# project_8.net
KiCad netlist of a schematic drawn in Altium Designer
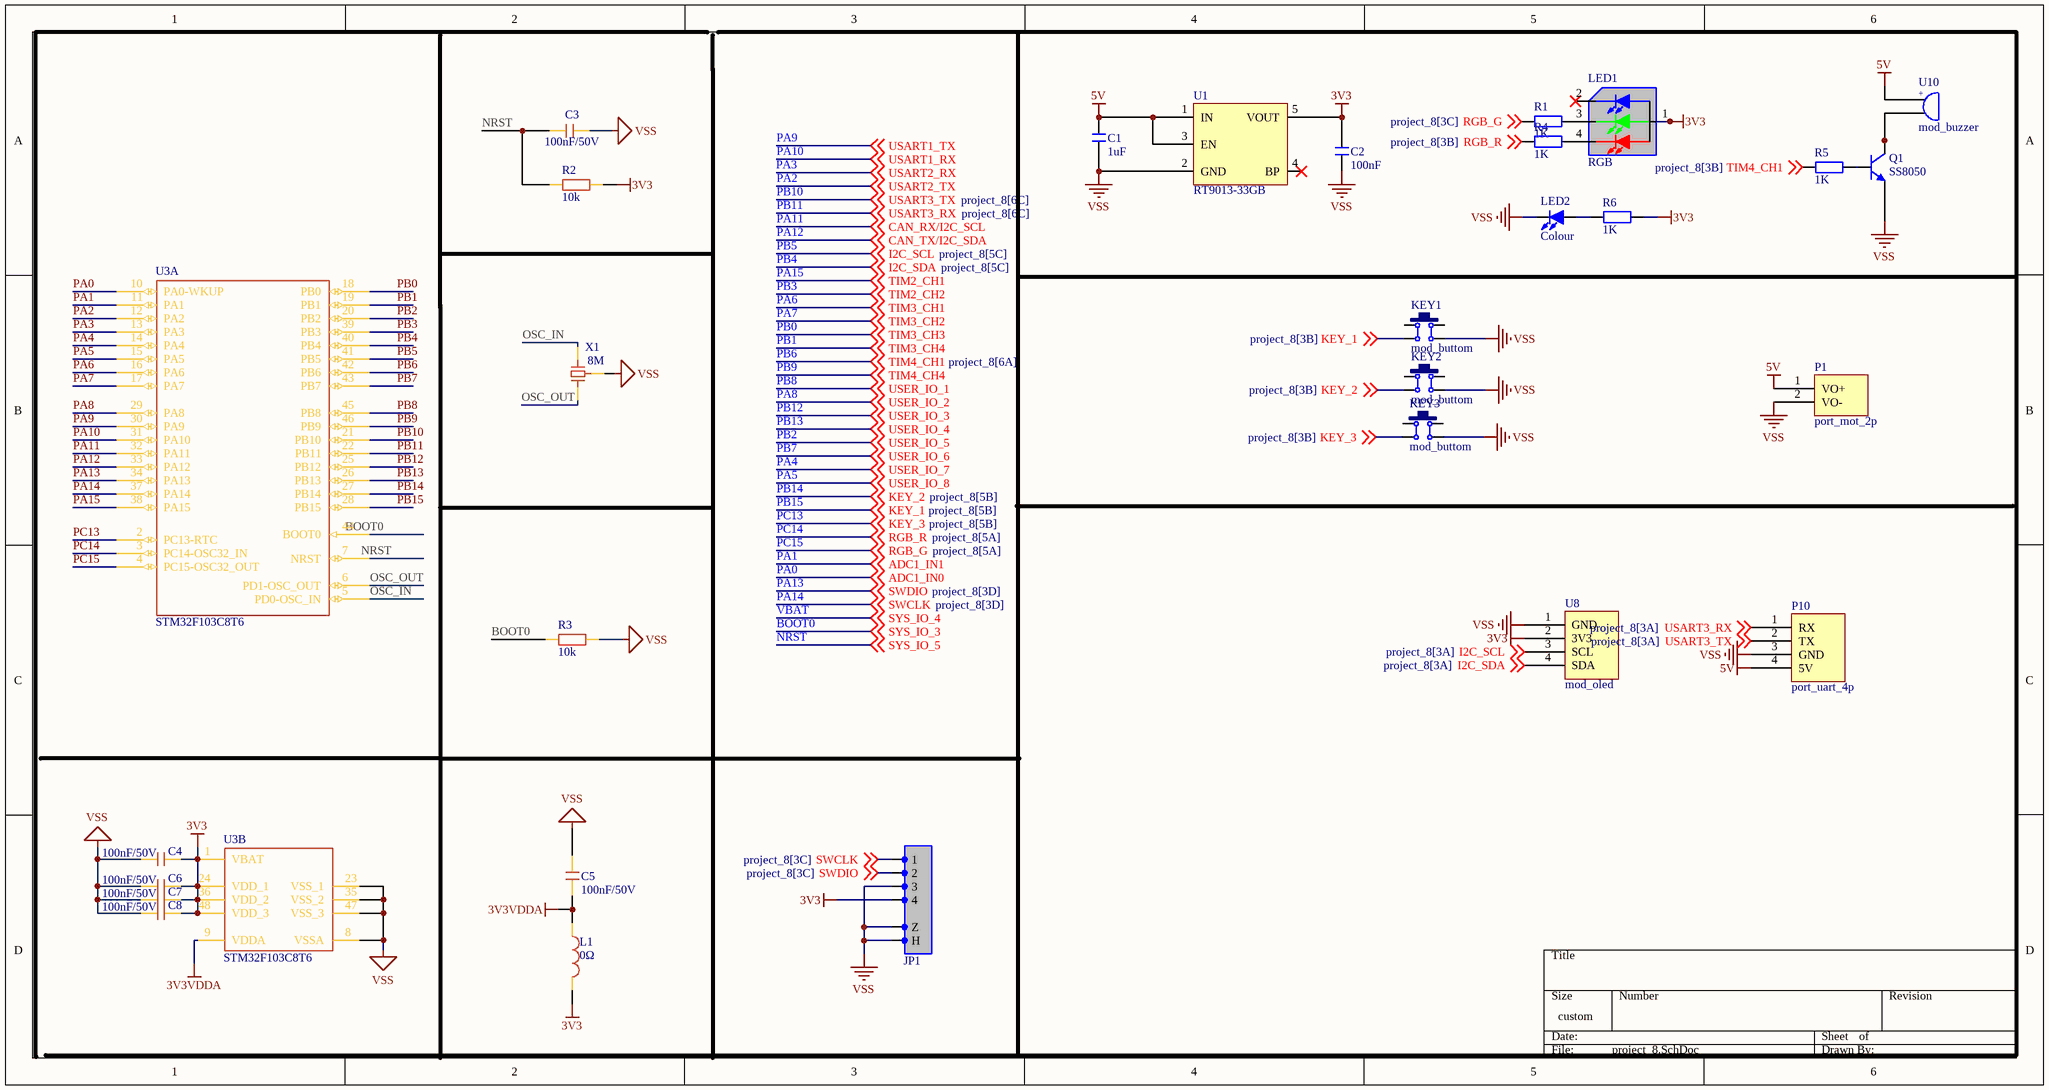
[diagram p0: project_8.SchDoc]

(export (version "E")
  (design (tool "Eeschema 10.0.6"))
  (components
    (comp (ref "C1")
      (value "1uF")
      (footprint "C 0603_L")
      (description "无极性贴片电容")
      (fields (field (name "版权归属") "源创客"))
      (libsource (lib "3.2-电容") (part "C"))
    )
    (comp (ref "C2")
      (value "100nF")
      (footprint "C 0603_L")
      (description "无极性贴片电容")
      (fields (field (name "版权归属") "源创客"))
      (libsource (lib "3.2-电容") (part "C"))
    )
    (comp (ref "C3")
      (value "100nF/50V")
      (footprint "C 0603_L")
      (description "贴片电容")
      (libsource (lib "Propitious Clouds_SCHLIB") (part "无极贴片电容"))
    )
    (comp (ref "C4")
      (value "100nF/50V")
      (footprint "C 0603_L")
      (description "贴片电容")
      (libsource (lib "Propitious Clouds_SCHLIB") (part "无极贴片电容"))
    )
    (comp (ref "C5")
      (value "100nF/50V")
      (footprint "C 0603_L")
      (description "贴片电容")
      (libsource (lib "Propitious Clouds_SCHLIB") (part "无极贴片电容"))
    )
    (comp (ref "C6")
      (value "100nF/50V")
      (footprint "C 0603_L")
      (description "贴片电容")
      (libsource (lib "Propitious Clouds_SCHLIB") (part "无极贴片电容"))
    )
    (comp (ref "C7")
      (value "100nF/50V")
      (footprint "C 0603_L")
      (description "贴片电容")
      (libsource (lib "Propitious Clouds_SCHLIB") (part "无极贴片电容"))
    )
    (comp (ref "C8")
      (value "100nF/50V")
      (footprint "C 0603_L")
      (description "贴片电容")
      (libsource (lib "Propitious Clouds_SCHLIB") (part "无极贴片电容"))
    )
    (comp (ref "JP1")
      (value "HDR-1X4")
      (footprint "GH 1.25-WS-4P")
      (description "4P接插件")
      (fields (field (name "版权归属") "源创客"))
      (libsource (lib "14.3-接插件-脚距1.25") (part "Header 4"))
    )
    (comp (ref "KEY1")
      (value "mod_buttom")
      (footprint "MOD_BUTTOM")
      (description "6*6*4.3按键")
      (libsource (lib "userLib") (part "mod_buttom"))
    )
    (comp (ref "KEY2")
      (value "mod_buttom")
      (footprint "MOD_BUTTOM")
      (description "6*6*4.3按键")
      (libsource (lib "userLib") (part "mod_buttom"))
    )
    (comp (ref "KEY3")
      (value "mod_buttom")
      (footprint "MOD_BUTTOM")
      (description "6*6*4.3按键")
      (libsource (lib "userLib") (part "mod_buttom"))
    )
    (comp (ref "L1")
      (value "0Ω")
      (footprint "L 0603")
      (description "小功率贴片电感")
      (libsource (lib "Propitious Clouds_SCHLIB") (part "磁珠"))
    )
    (comp (ref "LED1")
      (value "RGB")
      (footprint "LED 3528-RGB")
      (description "共阳三基色LED")
      (fields (field (name "版权归属") "源创客"))
      (libsource (lib "7.1-LED") (part "LED-RGB-A"))
    )
    (comp (ref "LED2")
      (value "Colour")
      (footprint "LED 0603R")
      (description "贴片LED")
      (fields (field (name "版权归属") "源创客"))
      (libsource (lib "7.1-LED") (part "LED-SMD"))
    )
    (comp (ref "P1")
      (value "port_mot_2p")
      (footprint "XH2.54_2P")
      (description "开环直流电机接口\r\nXH2.54弯排针2p")
      (libsource (lib "userLib") (part "port_mot_2p"))
    )
    (comp (ref "P10")
      (value "port_uart_4p")
      (footprint "XH2.54_4P")
      (description "串口接口/SPP蓝牙模块\r\nXH2.54弯排针4p/4p排母")
      (libsource (lib "userLib") (part "port_uart_4p"))
    )
    (comp (ref "Q1")
      (value "SS8050")
      (footprint "SOT23-3L")
      (description "高频放大-NPN型")
      (fields (field (name "版权归属") "源创客"))
      (libsource (lib "5.1-三极管") (part "8050-SMD"))
    )
    (comp (ref "R1")
      (value "1K")
      (footprint "R 0603_L")
      (description "贴片电阻")
      (fields (field (name "版权归属") "源创客"))
      (libsource (lib "3.1-电阻") (part "R"))
    )
    (comp (ref "R2")
      (value "10k")
      (footprint "R 0603_L")
      (description "贴片电阻1%精度")
      (libsource (lib "Propitious Clouds_SCHLIB") (part "电阻"))
    )
    (comp (ref "R3")
      (value "10k")
      (footprint "R 0603_L")
      (description "贴片电阻1%精度")
      (libsource (lib "Propitious Clouds_SCHLIB") (part "电阻"))
    )
    (comp (ref "R4")
      (value "1K")
      (footprint "R 0603_L")
      (description "贴片电阻")
      (fields (field (name "版权归属") "源创客"))
      (libsource (lib "3.1-电阻") (part "R"))
    )
    (comp (ref "R5")
      (value "1K")
      (footprint "R 0603_L")
      (description "贴片电阻")
      (fields (field (name "版权归属") "源创客"))
      (libsource (lib "3.1-电阻") (part "R"))
    )
    (comp (ref "R6")
      (value "1K")
      (footprint "R 0603_L")
      (description "贴片电阻")
      (fields (field (name "版权归属") "源创客"))
      (libsource (lib "3.1-电阻") (part "R"))
    )
    (comp (ref "U1")
      (value "RT9013-33GB")
      (footprint "SOT23-5")
      (libsource (lib "Schlib1") (part "RT9193-33GB"))
    )
    (comp (ref "U3")
      (value "STM32F103C8T6")
      (footprint "LQFP48 7X7_L")
      (description "STM32F103C8T6是一款由意法半导体公司（ST）推出的基于Cortex-M3内核的32位微控制器，硬件采用LQFP48封装，属于ST公司微控制器中的STM32系列。")
      (libsource (lib "Propitious Clouds_SCHLIB") (part "STM32F103C8T6"))
    )
    (comp (ref "U8")
      (value "mod_oled")
      (footprint "MOD_OLED")
      (description "oled模块\r\n4p排母")
      (libsource (lib "userLib") (part "mod_oled"))
    )
    (comp (ref "U10")
      (value "mod_buzzer")
      (footprint "MOD_BUZZER")
      (description "有源蜂鸣器")
      (libsource (lib "userLib") (part "mod_buzzer"))
    )
    (comp (ref "X1")
      (value "8M")
      (footprint "OSC 3213-3P")
      (description "3脚内置电容无源晶振")
      (libsource (lib "Propitious Clouds_SCHLIB") (part "XTAL-3P"))
    )
  )
  (nets
    (net (code "1") (name "/OSC_IN") (class "Default")
      (node (ref "U3") (pin "5") (pinfunction "PD0-OSC_IN_5") (pintype "bidirectional"))
      (node (ref "X1") (pin "2") (pinfunction "2_2") (pintype "passive"))
    )
    (net (code "2") (name "/OSC_OUT") (class "Default")
      (node (ref "U3") (pin "6") (pinfunction "PD1-OSC_OUT_6") (pintype "bidirectional"))
      (node (ref "X1") (pin "1") (pinfunction "1_1") (pintype "passive"))
    )
    (net (code "3") (name "/PA3") (class "Default")
      (node (ref "U3") (pin "13") (pinfunction "PA3_13") (pintype "bidirectional"))
    )
    (net (code "4") (name "3V3") (class "Default")
      (node (ref "C2") (pin "1") (pinfunction "1_1") (pintype "passive"))
      (node (ref "C4") (pin "2") (pinfunction "2_2") (pintype "passive"))
      (node (ref "C6") (pin "2") (pinfunction "2_2") (pintype "passive"))
      (node (ref "C7") (pin "2") (pinfunction "2_2") (pintype "passive"))
      (node (ref "C8") (pin "2") (pinfunction "2_2") (pintype "passive"))
      (node (ref "JP1") (pin "4") (pinfunction "4_4") (pintype "passive"))
      (node (ref "L1") (pin "2") (pinfunction "2_2") (pintype "passive"))
      (node (ref "LED1") (pin "1") (pintype "passive"))
      (node (ref "R2") (pin "2") (pinfunction "2_2") (pintype "passive"))
      (node (ref "R6") (pin "2") (pinfunction "2_2") (pintype "passive"))
      (node (ref "U1") (pin "5") (pinfunction "VOUT_5") (pintype "passive"))
      (node (ref "U3") (pin "1") (pinfunction "VBAT_1") (pintype "power_in"))
      (node (ref "U3") (pin "24") (pinfunction "VDD_1_24") (pintype "power_in"))
      (node (ref "U3") (pin "36") (pinfunction "VDD_2_36") (pintype "power_in"))
      (node (ref "U3") (pin "48") (pinfunction "VDD_3_48") (pintype "power_in"))
      (node (ref "U8") (pin "2") (pinfunction "3V3_2") (pintype "passive"))
    )
    (net (code "5") (name "3V3VDDA") (class "Default")
      (node (ref "C5") (pin "2") (pinfunction "2_2") (pintype "passive"))
      (node (ref "L1") (pin "1") (pinfunction "1_1") (pintype "passive"))
      (node (ref "U3") (pin "9") (pinfunction "VDDA_9") (pintype "power_in"))
    )
    (net (code "6") (name "5V") (class "Default")
      (node (ref "C1") (pin "1") (pinfunction "1_1") (pintype "passive"))
      (node (ref "P1") (pin "1") (pinfunction "VO+_1") (pintype "passive"))
      (node (ref "P10") (pin "4") (pinfunction "5V_4") (pintype "passive"))
      (node (ref "U1") (pin "1") (pinfunction "IN_1") (pintype "passive"))
      (node (ref "U1") (pin "3") (pinfunction "EN_3") (pintype "passive"))
      (node (ref "U10") (pin "1") (pinfunction "1_1") (pintype "passive"))
    )
    (net (code "7") (name "ADC1_IN0") (class "Default")
      (node (ref "U3") (pin "10") (pinfunction "PA0-WKUP_10") (pintype "bidirectional"))
    )
    (net (code "8") (name "ADC1_IN1") (class "Default")
      (node (ref "U3") (pin "11") (pinfunction "PA1_11") (pintype "bidirectional"))
    )
    (net (code "9") (name "CAN_RX{slash}I2C_SCL") (class "Default")
      (node (ref "U3") (pin "32") (pinfunction "PA11_32") (pintype "bidirectional"))
    )
    (net (code "10") (name "CAN_TX{slash}I2C_SDA") (class "Default")
      (node (ref "U3") (pin "33") (pinfunction "PA12_33") (pintype "bidirectional"))
    )
    (net (code "11") (name "I2C_SCL") (class "Default")
      (node (ref "U3") (pin "41") (pinfunction "PB5_41") (pintype "bidirectional"))
      (node (ref "U8") (pin "3") (pinfunction "SCL_3") (pintype "passive"))
    )
    (net (code "12") (name "I2C_SDA") (class "Default")
      (node (ref "U3") (pin "40") (pinfunction "PB4_40") (pintype "bidirectional"))
      (node (ref "U8") (pin "4") (pinfunction "SDA_4") (pintype "passive"))
    )
    (net (code "13") (name "KEY_1") (class "Default")
      (node (ref "KEY1") (pin "4") (pinfunction "4_4") (pintype "passive"))
      (node (ref "U3") (pin "28") (pinfunction "PB15_28") (pintype "bidirectional"))
    )
    (net (code "14") (name "KEY_2") (class "Default")
      (node (ref "KEY2") (pin "4") (pinfunction "4_4") (pintype "passive"))
      (node (ref "U3") (pin "27") (pinfunction "PB14_27") (pintype "bidirectional"))
    )
    (net (code "15") (name "KEY_3") (class "Default")
      (node (ref "KEY3") (pin "4") (pinfunction "4_4") (pintype "passive"))
      (node (ref "U3") (pin "2") (pinfunction "PC13-RTC_2") (pintype "bidirectional"))
    )
    (net (code "16") (name "Net-(LED1-Pad3)") (class "Default")
      (node (ref "LED1") (pin "3") (pintype "passive"))
      (node (ref "R1") (pin "2") (pinfunction "2_2") (pintype "passive"))
    )
    (net (code "17") (name "Net-(LED1-Pad4)") (class "Default")
      (node (ref "LED1") (pin "4") (pintype "passive"))
      (node (ref "R4") (pin "2") (pinfunction "2_2") (pintype "passive"))
    )
    (net (code "18") (name "Net-(LED2-A)") (class "Default")
      (node (ref "LED2") (pin "1") (pinfunction "A_1") (pintype "passive"))
      (node (ref "R6") (pin "1") (pinfunction "1_1") (pintype "passive"))
    )
    (net (code "19") (name "Net-(Q1-B)") (class "Default")
      (node (ref "Q1") (pin "1") (pinfunction "B_1") (pintype "passive"))
      (node (ref "R5") (pin "2") (pinfunction "2_2") (pintype "passive"))
    )
    (net (code "20") (name "Net-(Q1-C)") (class "Default")
      (node (ref "Q1") (pin "3") (pinfunction "C_3") (pintype "passive"))
      (node (ref "U10") (pin "2") (pinfunction "2_2") (pintype "passive"))
    )
    (net (code "21") (name "RGB_G") (class "Default")
      (node (ref "R1") (pin "1") (pinfunction "1_1") (pintype "passive"))
      (node (ref "U3") (pin "4") (pinfunction "PC15-OSC32_OUT_4") (pintype "bidirectional"))
    )
    (net (code "22") (name "RGB_R") (class "Default")
      (node (ref "R4") (pin "1") (pinfunction "1_1") (pintype "passive"))
      (node (ref "U3") (pin "3") (pinfunction "PC14-OSC32_IN_3") (pintype "bidirectional"))
    )
    (net (code "23") (name "SWCLK") (class "Default")
      (node (ref "JP1") (pin "1") (pinfunction "1_1") (pintype "passive"))
      (node (ref "U3") (pin "37") (pinfunction "PA14_37") (pintype "bidirectional"))
    )
    (net (code "24") (name "SWDIO") (class "Default")
      (node (ref "JP1") (pin "2") (pinfunction "2_2") (pintype "passive"))
      (node (ref "U3") (pin "34") (pinfunction "PA13_34") (pintype "bidirectional"))
    )
    (net (code "25") (name "SYS_IO_3") (class "Default")
      (node (ref "R3") (pin "1") (pinfunction "1_1") (pintype "passive"))
      (node (ref "U3") (pin "44") (pinfunction "BOOT0_44") (pintype "input"))
    )
    (net (code "27") (name "SYS_IO_5") (class "Default")
      (node (ref "C3") (pin "1") (pinfunction "1_1") (pintype "passive"))
      (node (ref "R2") (pin "1") (pinfunction "1_1") (pintype "passive"))
      (node (ref "U3") (pin "7") (pinfunction "NRST_7") (pintype "bidirectional"))
    )
    (net (code "28") (name "TIM2_CH1") (class "Default")
      (node (ref "U3") (pin "38") (pinfunction "PA15_38") (pintype "bidirectional"))
    )
    (net (code "29") (name "TIM2_CH2") (class "Default")
      (node (ref "U3") (pin "39") (pinfunction "PB3_39") (pintype "bidirectional"))
    )
    (net (code "30") (name "TIM3_CH1") (class "Default")
      (node (ref "U3") (pin "16") (pinfunction "PA6_16") (pintype "bidirectional"))
    )
    (net (code "31") (name "TIM3_CH2") (class "Default")
      (node (ref "U3") (pin "17") (pinfunction "PA7_17") (pintype "bidirectional"))
    )
    (net (code "32") (name "TIM3_CH3") (class "Default")
      (node (ref "U3") (pin "18") (pinfunction "PB0_18") (pintype "bidirectional"))
    )
    (net (code "33") (name "TIM3_CH4") (class "Default")
      (node (ref "U3") (pin "19") (pinfunction "PB1_19") (pintype "bidirectional"))
    )
    (net (code "34") (name "TIM4_CH1") (class "Default")
      (node (ref "R5") (pin "1") (pinfunction "1_1") (pintype "passive"))
      (node (ref "U3") (pin "42") (pinfunction "PB6_42") (pintype "bidirectional"))
    )
    (net (code "35") (name "TIM4_CH4") (class "Default")
      (node (ref "U3") (pin "46") (pinfunction "PB9_46") (pintype "bidirectional"))
    )
    (net (code "36") (name "USART1_RX") (class "Default")
      (node (ref "U3") (pin "31") (pinfunction "PA10_31") (pintype "bidirectional"))
    )
    (net (code "37") (name "USART1_TX") (class "Default")
      (node (ref "U3") (pin "30") (pinfunction "PA9_30") (pintype "bidirectional"))
    )
    (net (code "39") (name "USART2_TX") (class "Default")
      (node (ref "U3") (pin "12") (pinfunction "PA2_12") (pintype "bidirectional"))
    )
    (net (code "40") (name "USART3_RX") (class "Default")
      (node (ref "P10") (pin "1") (pinfunction "RX_1") (pintype "passive"))
      (node (ref "U3") (pin "22") (pinfunction "PB11_22") (pintype "bidirectional"))
    )
    (net (code "41") (name "USART3_TX") (class "Default")
      (node (ref "P10") (pin "2") (pinfunction "TX_2") (pintype "passive"))
      (node (ref "U3") (pin "21") (pinfunction "PB10_21") (pintype "bidirectional"))
    )
    (net (code "42") (name "USER_IO_1") (class "Default")
      (node (ref "U3") (pin "45") (pinfunction "PB8_45") (pintype "bidirectional"))
    )
    (net (code "43") (name "USER_IO_2") (class "Default")
      (node (ref "U3") (pin "29") (pinfunction "PA8_29") (pintype "bidirectional"))
    )
    (net (code "44") (name "USER_IO_3") (class "Default")
      (node (ref "U3") (pin "25") (pinfunction "PB12_25") (pintype "bidirectional"))
    )
    (net (code "45") (name "USER_IO_4") (class "Default")
      (node (ref "U3") (pin "26") (pinfunction "PB13_26") (pintype "bidirectional"))
    )
    (net (code "46") (name "USER_IO_5") (class "Default")
      (node (ref "U3") (pin "20") (pinfunction "PB2_20") (pintype "bidirectional"))
    )
    (net (code "47") (name "USER_IO_6") (class "Default")
      (node (ref "U3") (pin "43") (pinfunction "PB7_43") (pintype "bidirectional"))
    )
    (net (code "48") (name "USER_IO_7") (class "Default")
      (node (ref "U3") (pin "14") (pinfunction "PA4_14") (pintype "bidirectional"))
    )
    (net (code "49") (name "USER_IO_8") (class "Default")
      (node (ref "U3") (pin "15") (pinfunction "PA5_15") (pintype "bidirectional"))
    )
    (net (code "50") (name "VSS") (class "Default")
      (node (ref "C1") (pin "2") (pinfunction "2_2") (pintype "passive"))
      (node (ref "C2") (pin "2") (pinfunction "2_2") (pintype "passive"))
      (node (ref "C3") (pin "2") (pinfunction "2_2") (pintype "passive"))
      (node (ref "C4") (pin "1") (pinfunction "1_1") (pintype "passive"))
      (node (ref "C5") (pin "1") (pinfunction "1_1") (pintype "passive"))
      (node (ref "C6") (pin "1") (pinfunction "1_1") (pintype "passive"))
      (node (ref "C7") (pin "1") (pinfunction "1_1") (pintype "passive"))
      (node (ref "C8") (pin "1") (pinfunction "1_1") (pintype "passive"))
      (node (ref "JP1") (pin "0") (pinfunction "Z_0") (pintype "passive"))
      (node (ref "JP1") (pin "100") (pinfunction "H_100") (pintype "passive"))
      (node (ref "JP1") (pin "3") (pinfunction "3_3") (pintype "passive"))
      (node (ref "KEY1") (pin "3") (pinfunction "3_3") (pintype "passive"))
      (node (ref "KEY2") (pin "3") (pinfunction "3_3") (pintype "passive"))
      (node (ref "KEY3") (pin "3") (pinfunction "3_3") (pintype "passive"))
      (node (ref "LED2") (pin "2") (pinfunction "K_2") (pintype "passive"))
      (node (ref "P1") (pin "2") (pinfunction "VO-_2") (pintype "passive"))
      (node (ref "P10") (pin "3") (pinfunction "GND_3") (pintype "passive"))
      (node (ref "Q1") (pin "2") (pinfunction "E_2") (pintype "passive"))
      (node (ref "R3") (pin "2") (pinfunction "2_2") (pintype "passive"))
      (node (ref "U1") (pin "2") (pinfunction "GND_2") (pintype "passive"))
      (node (ref "U3") (pin "23") (pinfunction "VSS_1_23") (pintype "power_in"))
      (node (ref "U3") (pin "35") (pinfunction "VSS_2_35") (pintype "power_in"))
      (node (ref "U3") (pin "47") (pinfunction "VSS_3_47") (pintype "power_in"))
      (node (ref "U3") (pin "8") (pinfunction "VSSA_8") (pintype "power_in"))
      (node (ref "U8") (pin "1") (pinfunction "GND_1") (pintype "passive"))
      (node (ref "X1") (pin "3") (pinfunction "3_3") (pintype "passive"))
    )
    (net (code "51") (name "unconnected-(KEY1-Pad1)") (class "Default")
      (node (ref "KEY1") (pin "1") (pinfunction "1_1") (pintype "passive"))
    )
    (net (code "52") (name "unconnected-(KEY1-Pad2)") (class "Default")
      (node (ref "KEY1") (pin "2") (pinfunction "2_2") (pintype "passive"))
    )
    (net (code "53") (name "unconnected-(KEY2-Pad1)") (class "Default")
      (node (ref "KEY2") (pin "1") (pinfunction "1_1") (pintype "passive"))
    )
    (net (code "54") (name "unconnected-(KEY2-Pad2)") (class "Default")
      (node (ref "KEY2") (pin "2") (pinfunction "2_2") (pintype "passive"))
    )
    (net (code "55") (name "unconnected-(KEY3-Pad1)") (class "Default")
      (node (ref "KEY3") (pin "1") (pinfunction "1_1") (pintype "passive"))
    )
    (net (code "56") (name "unconnected-(KEY3-Pad2)") (class "Default")
      (node (ref "KEY3") (pin "2") (pinfunction "2_2") (pintype "passive"))
    )
    (net (code "57") (name "unconnected-(LED1-Pad2)") (class "Default")
      (node (ref "LED1") (pin "2") (pintype "passive+no_connect"))
    )
    (net (code "58") (name "unconnected-(U1-BP-Pad4)") (class "Default")
      (node (ref "U1") (pin "4") (pinfunction "BP_4") (pintype "passive+no_connect"))
    )
  )
)
